# LLmod1.net
KiCad netlist of a schematic drawn in EAGLE
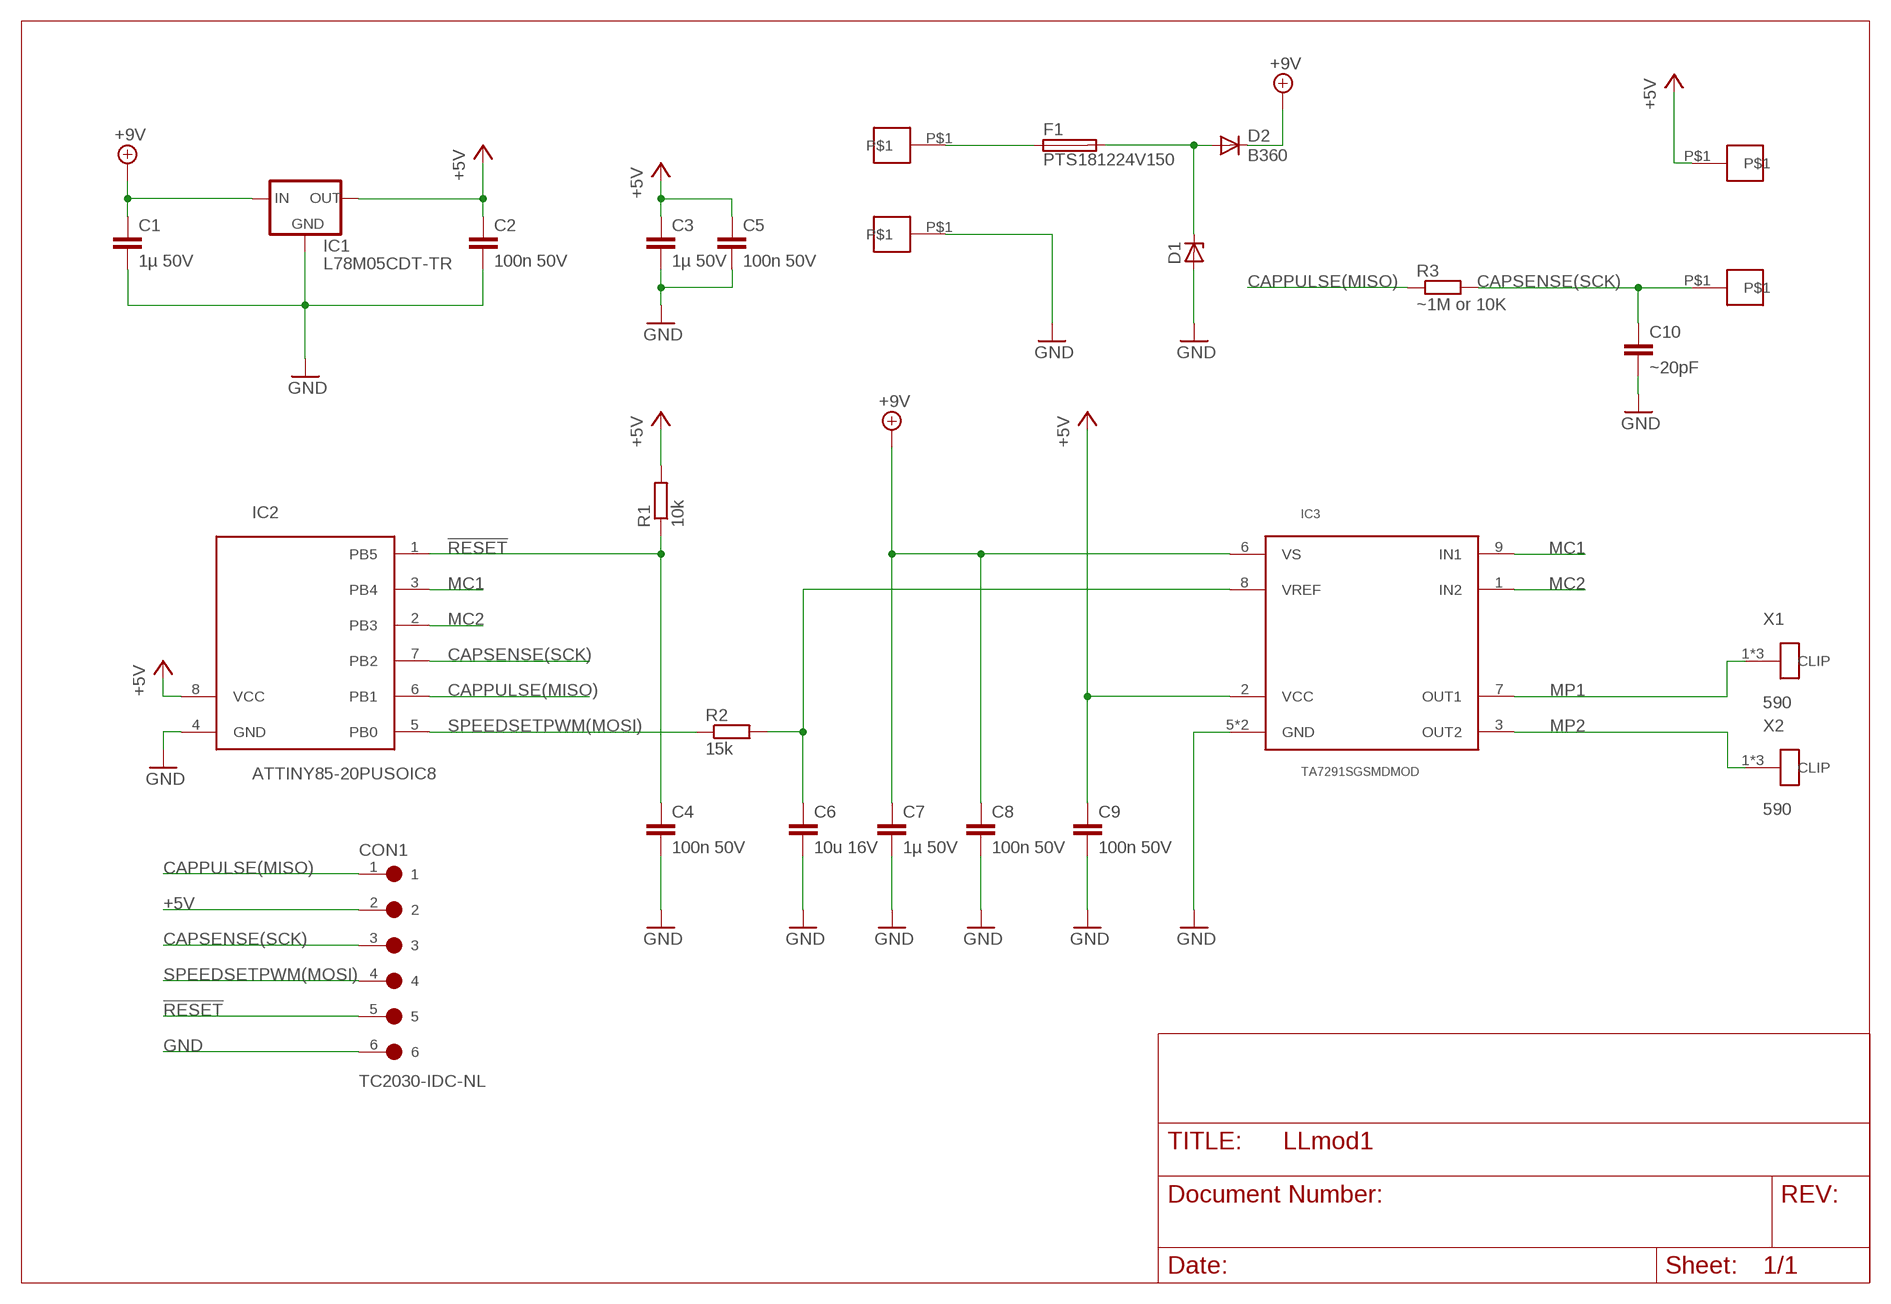
[diagram p0: schematic, sheet 1]

(export (version "E")
  (design (tool "Eeschema 10.0.6"))
  (components
    (comp (ref "+5V")
      (value "SOLPADSMALLMILL")
      (footprint "eagle-import:SINGLE-PAD-MED-SMALLMILL")
      (libsource (lib "eagle-import") (part "SOLPADSMALLMILL"))
    )
    (comp (ref "BTN")
      (value "SOLPADSMALLMILL")
      (footprint "eagle-import:SINGLE-PAD-MED-SMALLMILL")
      (libsource (lib "eagle-import") (part "SOLPADSMALLMILL"))
    )
    (comp (ref "C1")
      (value "1µ 50V")
      (footprint "eagle-import:C0805")
      (libsource (lib "eagle-import") (part "C-EUC0805"))
    )
    (comp (ref "C2")
      (value "100n 50V")
      (footprint "eagle-import:C0402")
      (libsource (lib "eagle-import") (part "C-EUC0402"))
    )
    (comp (ref "C3")
      (value "1µ 50V")
      (footprint "eagle-import:C0805")
      (libsource (lib "eagle-import") (part "C-EUC0805"))
    )
    (comp (ref "C4")
      (value "100n 50V")
      (footprint "eagle-import:C0402")
      (libsource (lib "eagle-import") (part "C-EUC0402"))
    )
    (comp (ref "C5")
      (value "100n 50V")
      (footprint "eagle-import:C0402")
      (libsource (lib "eagle-import") (part "C-EUC0402"))
    )
    (comp (ref "C6")
      (value "10u 16V")
      (footprint "eagle-import:C0805")
      (libsource (lib "eagle-import") (part "C-EUC0805"))
    )
    (comp (ref "C7")
      (value "1µ 50V")
      (footprint "eagle-import:C0805")
      (libsource (lib "eagle-import") (part "C-EUC0805"))
    )
    (comp (ref "C8")
      (value "100n 50V")
      (footprint "eagle-import:C0402")
      (libsource (lib "eagle-import") (part "C-EUC0402"))
    )
    (comp (ref "C9")
      (value "100n 50V")
      (footprint "eagle-import:C0402")
      (libsource (lib "eagle-import") (part "C-EUC0402"))
    )
    (comp (ref "C10")
      (value "~20pF")
      (footprint "eagle-import:C0402")
      (libsource (lib "eagle-import") (part "C-EUC0402"))
    )
    (comp (ref "CON1")
      (value "TC2030-IDC-NL")
      (footprint "eagle-import:TC2030-IDC-NL")
      (libsource (lib "eagle-import") (part "TC2030-IDC-NL"))
    )
    (comp (ref "D1")
      (value "ZENER-DIODESMB")
      (footprint "eagle-import:SMB")
      (libsource (lib "eagle-import") (part "ZENER-DIODESMB"))
    )
    (comp (ref "D2")
      (value "B360")
      (footprint "eagle-import:DO214AA")
      (libsource (lib "eagle-import") (part "DIODE-DO214AA"))
    )
    (comp (ref "F1")
      (value "PTS181224V150")
      (footprint "eagle-import:1812")
      (libsource (lib "eagle-import") (part "POLY1812"))
    )
    (comp (ref "GND")
      (value "SOLPAD")
      (footprint "eagle-import:SINGLE-PAD-MED")
      (libsource (lib "eagle-import") (part "SOLPAD"))
    )
    (comp (ref "IC1")
      (value "L78M05CDT-TR")
      (footprint "eagle-import:DPAK")
      (libsource (lib "eagle-import") (part "L78M05CDT-TR"))
    )
    (comp (ref "IC2")
      (value "ATTINY85-20PUSOIC8")
      (footprint "eagle-import:SOIC-8-5,3MM")
      (libsource (lib "eagle-import") (part "ATTINY85-20PUSOIC8"))
    )
    (comp (ref "IC3")
      (value "TA7291SGSMDMOD")
      (footprint "eagle-import:SIP9-SMDMOD")
      (libsource (lib "eagle-import") (part "TA7291SGSMDMOD"))
    )
    (comp (ref "R1")
      (value "10k")
      (footprint "eagle-import:R0402")
      (libsource (lib "eagle-import") (part "R-EU_R0402"))
    )
    (comp (ref "R2")
      (value "15k")
      (footprint "eagle-import:R0402")
      (libsource (lib "eagle-import") (part "R-EU_R0402"))
    )
    (comp (ref "R3")
      (value "~1M or 10K")
      (footprint "eagle-import:R0402")
      (libsource (lib "eagle-import") (part "R-EU_R0402"))
    )
    (comp (ref "VBAT")
      (value "SOLPAD")
      (footprint "eagle-import:SINGLE-PAD-MED")
      (libsource (lib "eagle-import") (part "SOLPAD"))
    )
    (comp (ref "X1")
      (value "590")
      (footprint "eagle-import:590K")
      (libsource (lib "eagle-import") (part "590"))
    )
    (comp (ref "X2")
      (value "590")
      (footprint "eagle-import:590K")
      (libsource (lib "eagle-import") (part "590"))
    )
  )
  (nets
    (net (code "1") (name "+5V") (class "Default")
      (node (ref "+5V") (pin "P$1") (pinfunction "P$1_P$1") (pintype "bidirectional"))
      (node (ref "C2") (pin "1") (pinfunction "1_1") (pintype "passive"))
      (node (ref "C3") (pin "1") (pinfunction "1_1") (pintype "passive"))
      (node (ref "C5") (pin "1") (pinfunction "1_1") (pintype "passive"))
      (node (ref "C9") (pin "1") (pinfunction "1_1") (pintype "passive"))
      (node (ref "CON1") (pin "2") (pinfunction "2_2") (pintype "passive"))
      (node (ref "IC1") (pin "P$3") (pinfunction "OUT_P$3") (pintype "passive"))
      (node (ref "IC2") (pin "8") (pinfunction "VCC_8") (pintype "bidirectional"))
      (node (ref "IC3") (pin "2") (pinfunction "VCC_2") (pintype "bidirectional"))
      (node (ref "R1") (pin "2") (pinfunction "2_2") (pintype "passive"))
    )
    (net (code "2") (name "+9V") (class "Default")
      (node (ref "C1") (pin "1") (pinfunction "1_1") (pintype "passive"))
      (node (ref "C7") (pin "1") (pinfunction "1_1") (pintype "passive"))
      (node (ref "C8") (pin "1") (pinfunction "1_1") (pintype "passive"))
      (node (ref "D2") (pin "C") (pinfunction "C_C") (pintype "passive"))
      (node (ref "IC1") (pin "P$2") (pinfunction "IN_P$2") (pintype "input"))
      (node (ref "IC3") (pin "6") (pinfunction "VS_6") (pintype "bidirectional"))
    )
    (net (code "3") (name "/CAPPULSE(MISO)") (class "Default")
      (node (ref "CON1") (pin "1") (pinfunction "1_1") (pintype "passive"))
      (node (ref "IC2") (pin "6") (pinfunction "PB1_6") (pintype "bidirectional"))
      (node (ref "R3") (pin "1") (pinfunction "1_1") (pintype "passive"))
    )
    (net (code "4") (name "/CAPSENSE(SCK)") (class "Default")
      (node (ref "BTN") (pin "P$1") (pinfunction "P$1_P$1") (pintype "bidirectional"))
      (node (ref "C10") (pin "1") (pinfunction "1_1") (pintype "passive"))
      (node (ref "CON1") (pin "3") (pinfunction "3_3") (pintype "passive"))
      (node (ref "IC2") (pin "7") (pinfunction "PB2_7") (pintype "bidirectional"))
      (node (ref "R3") (pin "2") (pinfunction "2_2") (pintype "passive"))
    )
    (net (code "5") (name "/MC1") (class "Default")
      (node (ref "IC2") (pin "3") (pinfunction "PB4_3") (pintype "bidirectional"))
      (node (ref "IC3") (pin "9") (pinfunction "IN1_9") (pintype "bidirectional"))
    )
    (net (code "6") (name "/MC2") (class "Default")
      (node (ref "IC2") (pin "2") (pinfunction "PB3_2") (pintype "bidirectional"))
      (node (ref "IC3") (pin "1") (pinfunction "IN2_1") (pintype "bidirectional"))
    )
    (net (code "7") (name "/MP1") (class "Default")
      (node (ref "IC3") (pin "7") (pinfunction "OUT1_7") (pintype "bidirectional"))
      (node (ref "X1") (pin "1") (pinfunction "CLIP_1") (pintype "bidirectional"))
      (node (ref "X1") (pin "2") (pinfunction "CLIP_2") (pintype "bidirectional"))
      (node (ref "X1") (pin "3") (pinfunction "CLIP_3") (pintype "bidirectional"))
    )
    (net (code "8") (name "/MP2") (class "Default")
      (node (ref "IC3") (pin "3") (pinfunction "OUT2_3") (pintype "bidirectional"))
      (node (ref "X2") (pin "1") (pinfunction "CLIP_1") (pintype "bidirectional"))
      (node (ref "X2") (pin "2") (pinfunction "CLIP_2") (pintype "bidirectional"))
      (node (ref "X2") (pin "3") (pinfunction "CLIP_3") (pintype "bidirectional"))
    )
    (net (code "9") (name "/SPEEDSETPWM(MOSI)") (class "Default")
      (node (ref "CON1") (pin "4") (pinfunction "4_4") (pintype "passive"))
      (node (ref "IC2") (pin "5") (pinfunction "PB0_5") (pintype "bidirectional"))
      (node (ref "R2") (pin "1") (pinfunction "1_1") (pintype "passive"))
    )
    (net (code "10") (name "/~{RESET}") (class "Default")
      (node (ref "C4") (pin "1") (pinfunction "1_1") (pintype "passive"))
      (node (ref "CON1") (pin "5") (pinfunction "5_5") (pintype "passive"))
      (node (ref "IC2") (pin "1") (pinfunction "PB5_1") (pintype "bidirectional"))
      (node (ref "R1") (pin "1") (pinfunction "1_1") (pintype "passive"))
    )
    (net (code "11") (name "GND") (class "Default")
      (node (ref "C1") (pin "2") (pinfunction "2_2") (pintype "passive"))
      (node (ref "C10") (pin "2") (pinfunction "2_2") (pintype "passive"))
      (node (ref "C2") (pin "2") (pinfunction "2_2") (pintype "passive"))
      (node (ref "C3") (pin "2") (pinfunction "2_2") (pintype "passive"))
      (node (ref "C4") (pin "2") (pinfunction "2_2") (pintype "passive"))
      (node (ref "C5") (pin "2") (pinfunction "2_2") (pintype "passive"))
      (node (ref "C6") (pin "2") (pinfunction "2_2") (pintype "passive"))
      (node (ref "C7") (pin "2") (pinfunction "2_2") (pintype "passive"))
      (node (ref "C8") (pin "2") (pinfunction "2_2") (pintype "passive"))
      (node (ref "C9") (pin "2") (pinfunction "2_2") (pintype "passive"))
      (node (ref "CON1") (pin "6") (pinfunction "6_6") (pintype "passive"))
      (node (ref "D1") (pin "A") (pinfunction "A_A") (pintype "passive"))
      (node (ref "GND") (pin "P$1") (pinfunction "P$1_P$1") (pintype "bidirectional"))
      (node (ref "IC1") (pin "P$1") (pinfunction "GND_P$1") (pintype "input"))
      (node (ref "IC2") (pin "4") (pinfunction "GND_4") (pintype "bidirectional"))
      (node (ref "IC3") (pin "5") (pinfunction "GND_5") (pintype "bidirectional"))
      (node (ref "IC3") (pin "THERMAL") (pinfunction "GND_THERMAL") (pintype "bidirectional"))
    )
    (net (code "12") (name "Net-(D1-PadC)") (class "Default")
      (node (ref "D1") (pin "C") (pinfunction "C_C") (pintype "passive"))
      (node (ref "D2") (pin "A") (pinfunction "A_A") (pintype "passive"))
      (node (ref "F1") (pin "2") (pinfunction "2_2") (pintype "passive"))
    )
    (net (code "13") (name "Net-(F1-Pad1)") (class "Default")
      (node (ref "F1") (pin "1") (pinfunction "1_1") (pintype "passive"))
      (node (ref "VBAT") (pin "P$1") (pinfunction "P$1_P$1") (pintype "bidirectional"))
    )
    (net (code "14") (name "Net-(IC3-VREF)") (class "Default")
      (node (ref "C6") (pin "1") (pinfunction "1_1") (pintype "passive"))
      (node (ref "IC3") (pin "8") (pinfunction "VREF_8") (pintype "bidirectional"))
      (node (ref "R2") (pin "2") (pinfunction "2_2") (pintype "passive"))
    )
  )
)
